# v0_9.net
KiCad netlist of a schematic drawn in EAGLE
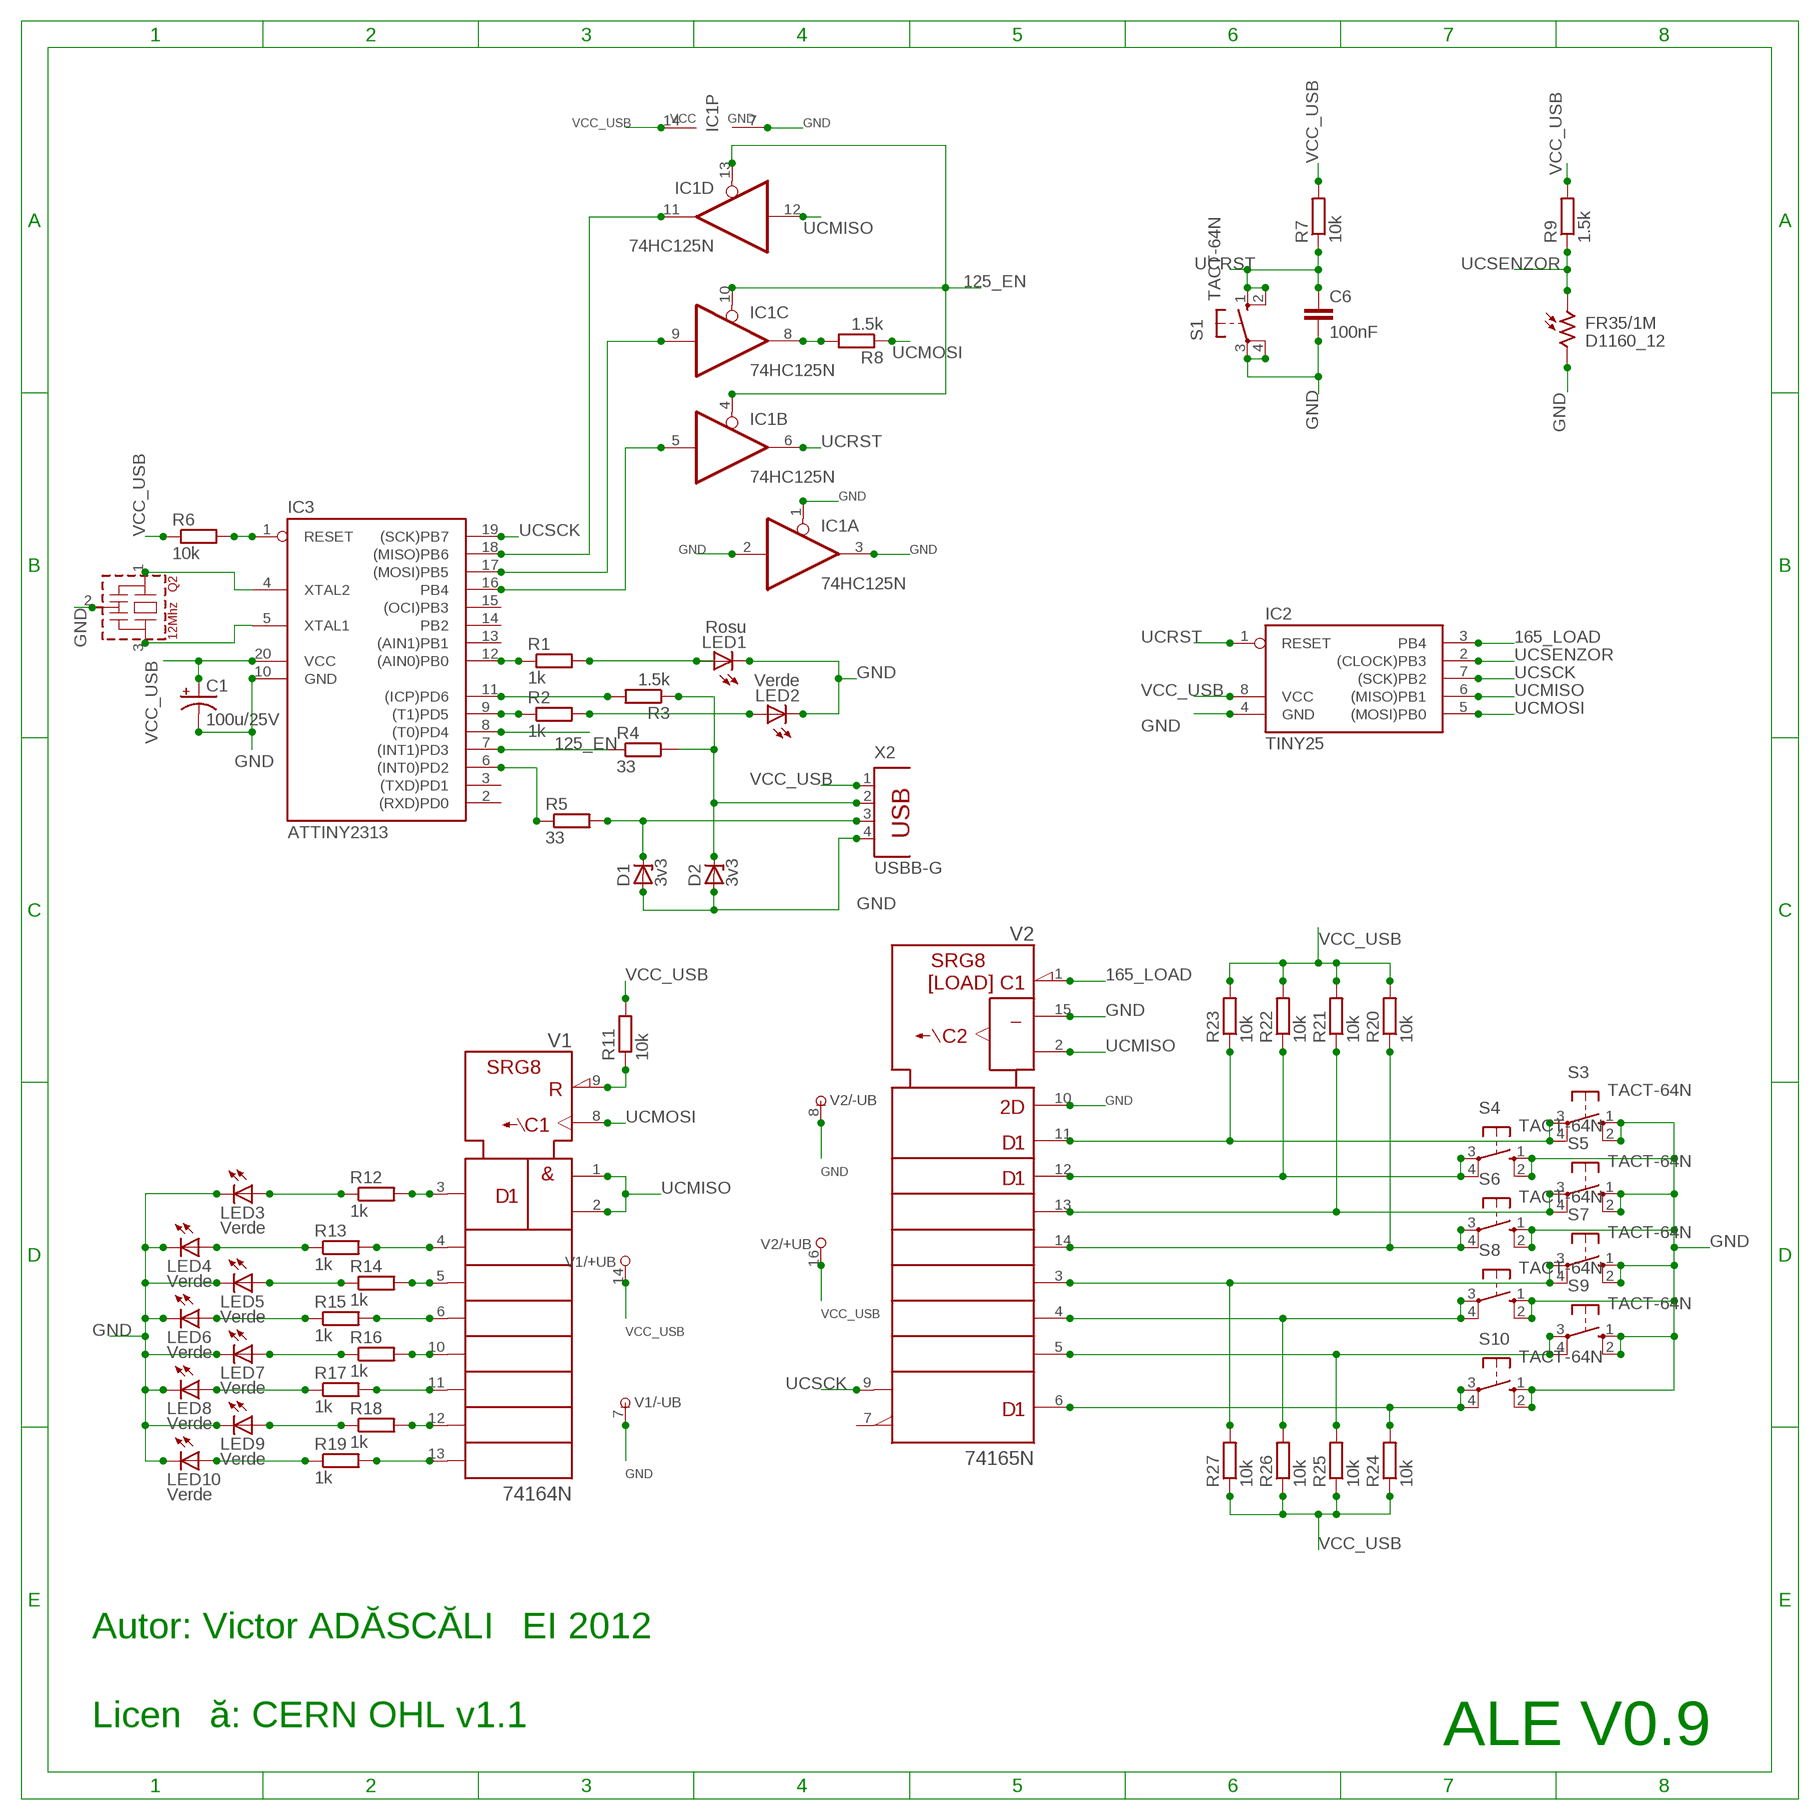
[diagram p0: schematic, sheet 1]

(export (version "E")
  (design (tool "Eeschema 10.0.6"))
  (components
    (comp (ref "C1")
      (value "100u/25V")
      (footprint "eagle-import:E2,5-6")
      (libsource (lib "eagle-import") (part "CPOL-USE2.5-6"))
    )
    (comp (ref "C6")
      (value "100nF")
      (footprint "eagle-import:C050-025X075")
      (libsource (lib "eagle-import") (part "C-EU050-025X075"))
    )
    (comp (ref "D1")
      (value "3v3")
      (footprint "eagle-import:ZDIO-7.5")
      (libsource (lib "eagle-import") (part "ZENER-DIODEZD-7.5"))
    )
    (comp (ref "D2")
      (value "3v3")
      (footprint "eagle-import:ZDIO-7.5")
      (libsource (lib "eagle-import") (part "ZENER-DIODEZD-7.5"))
    )
    (comp (ref "FR35/1M")
      (value "D1160_12")
      (footprint "eagle-import:D11XX")
      (libsource (lib "eagle-import") (part "D1160_12"))
    )
    (comp (ref "IC1")
      (value "74HC125N")
      (footprint "eagle-import:DIL14")
      (libsource (lib "eagle-import") (part "74125NAC"))
    )
    (comp (ref "IC2")
      (value "TINY25")
      (footprint "eagle-import:DIL08")
      (libsource (lib "eagle-import") (part "TINY22P"))
    )
    (comp (ref "IC3")
      (value "ATTINY2313")
      (footprint "eagle-import:DIL20")
      (libsource (lib "eagle-import") (part "AT90S2313P"))
    )
    (comp (ref "LED1")
      (value "Rosu")
      (footprint "eagle-import:LED3MM")
      (libsource (lib "eagle-import") (part "LED3MM"))
    )
    (comp (ref "LED2")
      (value "Verde")
      (footprint "eagle-import:LED3MM")
      (libsource (lib "eagle-import") (part "LED3MM"))
    )
    (comp (ref "LED3")
      (value "Verde")
      (footprint "eagle-import:LED3MM")
      (libsource (lib "eagle-import") (part "LED3MM"))
    )
    (comp (ref "LED4")
      (value "Verde")
      (footprint "eagle-import:LED3MM")
      (libsource (lib "eagle-import") (part "LED3MM"))
    )
    (comp (ref "LED5")
      (value "Verde")
      (footprint "eagle-import:LED3MM")
      (libsource (lib "eagle-import") (part "LED3MM"))
    )
    (comp (ref "LED6")
      (value "Verde")
      (footprint "eagle-import:LED3MM")
      (libsource (lib "eagle-import") (part "LED3MM"))
    )
    (comp (ref "LED7")
      (value "Verde")
      (footprint "eagle-import:LED3MM")
      (libsource (lib "eagle-import") (part "LED3MM"))
    )
    (comp (ref "LED8")
      (value "Verde")
      (footprint "eagle-import:LED3MM")
      (libsource (lib "eagle-import") (part "LED3MM"))
    )
    (comp (ref "LED9")
      (value "Verde")
      (footprint "eagle-import:LED3MM")
      (libsource (lib "eagle-import") (part "LED3MM"))
    )
    (comp (ref "LED10")
      (value "Verde")
      (footprint "eagle-import:LED3MM")
      (libsource (lib "eagle-import") (part "LED3MM"))
    )
    (comp (ref "Q2")
      (value "12Mhz")
      (footprint "eagle-import:CSTLS_X")
      (libsource (lib "eagle-import") (part "CSTLS_X"))
    )
    (comp (ref "R1")
      (value "1k")
      (footprint "eagle-import:0207_10")
      (libsource (lib "eagle-import") (part "R-EU_0207/10"))
    )
    (comp (ref "R2")
      (value "1k")
      (footprint "eagle-import:0204_5")
      (libsource (lib "eagle-import") (part "R-EU_0204/5"))
    )
    (comp (ref "R3")
      (value "1.5k")
      (footprint "eagle-import:0207_10")
      (libsource (lib "eagle-import") (part "R-EU_0207/10"))
    )
    (comp (ref "R4")
      (value "33")
      (footprint "eagle-import:0207_12")
      (libsource (lib "eagle-import") (part "R-EU_0207/12"))
    )
    (comp (ref "R5")
      (value "33")
      (footprint "eagle-import:0207_10")
      (libsource (lib "eagle-import") (part "R-EU_0207/10"))
    )
    (comp (ref "R6")
      (value "10k")
      (footprint "eagle-import:0207_10")
      (libsource (lib "eagle-import") (part "R-EU_0207/10"))
    )
    (comp (ref "R7")
      (value "10k")
      (footprint "eagle-import:0207_10")
      (libsource (lib "eagle-import") (part "R-EU_0207/10"))
    )
    (comp (ref "R8")
      (value "1.5k")
      (footprint "eagle-import:0207_10")
      (libsource (lib "eagle-import") (part "R-EU_0207/10"))
    )
    (comp (ref "R9")
      (value "1.5k")
      (footprint "eagle-import:0207_12")
      (libsource (lib "eagle-import") (part "R-EU_0207/12"))
    )
    (comp (ref "R11")
      (value "10k")
      (footprint "eagle-import:0207_15")
      (libsource (lib "eagle-import") (part "R-EU_0207/15"))
    )
    (comp (ref "R12")
      (value "1k")
      (footprint "eagle-import:0207_10")
      (libsource (lib "eagle-import") (part "R-EU_0207/10"))
    )
    (comp (ref "R13")
      (value "1k")
      (footprint "eagle-import:0207_10")
      (libsource (lib "eagle-import") (part "R-EU_0207/10"))
    )
    (comp (ref "R14")
      (value "1k")
      (footprint "eagle-import:0207_10")
      (libsource (lib "eagle-import") (part "R-EU_0207/10"))
    )
    (comp (ref "R15")
      (value "1k")
      (footprint "eagle-import:0207_10")
      (libsource (lib "eagle-import") (part "R-EU_0207/10"))
    )
    (comp (ref "R16")
      (value "1k")
      (footprint "eagle-import:0207_10")
      (libsource (lib "eagle-import") (part "R-EU_0207/10"))
    )
    (comp (ref "R17")
      (value "1k")
      (footprint "eagle-import:0207_10")
      (libsource (lib "eagle-import") (part "R-EU_0207/10"))
    )
    (comp (ref "R18")
      (value "1k")
      (footprint "eagle-import:0207_10")
      (libsource (lib "eagle-import") (part "R-EU_0207/10"))
    )
    (comp (ref "R19")
      (value "1k")
      (footprint "eagle-import:0207_10")
      (libsource (lib "eagle-import") (part "R-EU_0207/10"))
    )
    (comp (ref "R20")
      (value "10k")
      (footprint "eagle-import:0207_10")
      (libsource (lib "eagle-import") (part "R-EU_0207/10"))
    )
    (comp (ref "R21")
      (value "10k")
      (footprint "eagle-import:0207_10")
      (libsource (lib "eagle-import") (part "R-EU_0207/10"))
    )
    (comp (ref "R22")
      (value "10k")
      (footprint "eagle-import:0207_10")
      (libsource (lib "eagle-import") (part "R-EU_0207/10"))
    )
    (comp (ref "R23")
      (value "10k")
      (footprint "eagle-import:0207_10")
      (libsource (lib "eagle-import") (part "R-EU_0207/10"))
    )
    (comp (ref "R24")
      (value "10k")
      (footprint "eagle-import:0207_10")
      (libsource (lib "eagle-import") (part "R-EU_0207/10"))
    )
    (comp (ref "R25")
      (value "10k")
      (footprint "eagle-import:0207_10")
      (libsource (lib "eagle-import") (part "R-EU_0207/10"))
    )
    (comp (ref "R26")
      (value "10k")
      (footprint "eagle-import:0207_10")
      (libsource (lib "eagle-import") (part "R-EU_0207/10"))
    )
    (comp (ref "R27")
      (value "10k")
      (footprint "eagle-import:0207_10")
      (libsource (lib "eagle-import") (part "R-EU_0207/10"))
    )
    (comp (ref "S1")
      (value "TACT-64N")
      (footprint "eagle-import:B3F-10XX")
      (libsource (lib "eagle-import") (part "10-XX"))
    )
    (comp (ref "S3")
      (value "TACT-64N")
      (footprint "eagle-import:B3F-10XX")
      (libsource (lib "eagle-import") (part "10-XX"))
    )
    (comp (ref "S4")
      (value "TACT-64N")
      (footprint "eagle-import:B3F-10XX")
      (libsource (lib "eagle-import") (part "10-XX"))
    )
    (comp (ref "S5")
      (value "TACT-64N")
      (footprint "eagle-import:B3F-10XX")
      (libsource (lib "eagle-import") (part "10-XX"))
    )
    (comp (ref "S6")
      (value "TACT-64N")
      (footprint "eagle-import:B3F-10XX")
      (libsource (lib "eagle-import") (part "10-XX"))
    )
    (comp (ref "S7")
      (value "TACT-64N")
      (footprint "eagle-import:B3F-10XX")
      (libsource (lib "eagle-import") (part "10-XX"))
    )
    (comp (ref "S8")
      (value "TACT-64N")
      (footprint "eagle-import:B3F-10XX")
      (libsource (lib "eagle-import") (part "10-XX"))
    )
    (comp (ref "S9")
      (value "TACT-64N")
      (footprint "eagle-import:B3F-10XX")
      (libsource (lib "eagle-import") (part "10-XX"))
    )
    (comp (ref "S10")
      (value "TACT-64N")
      (footprint "eagle-import:B3F-10XX")
      (libsource (lib "eagle-import") (part "10-XX"))
    )
    (comp (ref "V1")
      (value "74164N")
      (footprint "eagle-import:DIL14")
      (libsource (lib "eagle-import") (part "74164N"))
    )
    (comp (ref "V2")
      (value "74165N")
      (footprint "eagle-import:DIL16")
      (libsource (lib "eagle-import") (part "74165N"))
    )
    (comp (ref "X2")
      (value "USBB-G")
      (footprint "eagle-import:PN61729")
      (libsource (lib "eagle-import") (part "PN61729"))
    )
  )
  (nets
    (net (code "1") (name "/125_EN") (class "Default")
      (node (ref "IC1") (pin "10") (pinfunction "OE_10") (pintype "input"))
      (node (ref "IC1") (pin "13") (pinfunction "OE_13") (pintype "input"))
      (node (ref "IC1") (pin "4") (pinfunction "OE_4") (pintype "input"))
      (node (ref "IC3") (pin "8") (pinfunction "(T0)PD4_8") (pintype "bidirectional"))
    )
    (net (code "2") (name "/165_LOAD") (class "Default")
      (node (ref "IC2") (pin "3") (pinfunction "PB4_3") (pintype "bidirectional"))
      (node (ref "V2") (pin "1") (pinfunction "SH/~{LD}_1") (pintype "input"))
    )
    (net (code "3") (name "/GND") (class "Default")
      (node (ref "C1") (pin "-") (pinfunction "-_-") (pintype "passive"))
      (node (ref "C6") (pin "2") (pinfunction "2_2") (pintype "passive"))
      (node (ref "D1") (pin "A") (pinfunction "A_A") (pintype "passive"))
      (node (ref "D2") (pin "A") (pinfunction "A_A") (pintype "passive"))
      (node (ref "FR35/1M") (pin "2") (pinfunction "2_2") (pintype "passive"))
      (node (ref "IC1") (pin "1") (pinfunction "OE_1") (pintype "input"))
      (node (ref "IC1") (pin "2") (pinfunction "I_2") (pintype "input"))
      (node (ref "IC1") (pin "3") (pinfunction "O_3") (pintype "tri_state"))
      (node (ref "IC1") (pin "7") (pinfunction "GND_7") (pintype "power_in"))
      (node (ref "IC2") (pin "4") (pinfunction "GND_4") (pintype "power_in"))
      (node (ref "IC3") (pin "10") (pinfunction "GND_10") (pintype "power_in"))
      (node (ref "LED1") (pin "K") (pinfunction "C_K") (pintype "passive"))
      (node (ref "LED10") (pin "K") (pinfunction "C_K") (pintype "passive"))
      (node (ref "LED2") (pin "K") (pinfunction "C_K") (pintype "passive"))
      (node (ref "LED3") (pin "K") (pinfunction "C_K") (pintype "passive"))
      (node (ref "LED4") (pin "K") (pinfunction "C_K") (pintype "passive"))
      (node (ref "LED5") (pin "K") (pinfunction "C_K") (pintype "passive"))
      (node (ref "LED6") (pin "K") (pinfunction "C_K") (pintype "passive"))
      (node (ref "LED7") (pin "K") (pinfunction "C_K") (pintype "passive"))
      (node (ref "LED8") (pin "K") (pinfunction "C_K") (pintype "passive"))
      (node (ref "LED9") (pin "K") (pinfunction "C_K") (pintype "passive"))
      (node (ref "Q2") (pin "2") (pinfunction "VSS_2") (pintype "power_in"))
      (node (ref "S1") (pin "3") (pinfunction "P_3") (pintype "passive"))
      (node (ref "S1") (pin "4") (pinfunction "P1_4") (pintype "passive"))
      (node (ref "S10") (pin "1") (pinfunction "S_1") (pintype "passive"))
      (node (ref "S10") (pin "2") (pinfunction "S1_2") (pintype "passive"))
      (node (ref "S3") (pin "1") (pinfunction "S_1") (pintype "passive"))
      (node (ref "S3") (pin "2") (pinfunction "S1_2") (pintype "passive"))
      (node (ref "S4") (pin "1") (pinfunction "S_1") (pintype "passive"))
      (node (ref "S4") (pin "2") (pinfunction "S1_2") (pintype "passive"))
      (node (ref "S5") (pin "1") (pinfunction "S_1") (pintype "passive"))
      (node (ref "S5") (pin "2") (pinfunction "S1_2") (pintype "passive"))
      (node (ref "S6") (pin "1") (pinfunction "S_1") (pintype "passive"))
      (node (ref "S6") (pin "2") (pinfunction "S1_2") (pintype "passive"))
      (node (ref "S7") (pin "1") (pinfunction "S_1") (pintype "passive"))
      (node (ref "S7") (pin "2") (pinfunction "S1_2") (pintype "passive"))
      (node (ref "S8") (pin "1") (pinfunction "S_1") (pintype "passive"))
      (node (ref "S8") (pin "2") (pinfunction "S1_2") (pintype "passive"))
      (node (ref "S9") (pin "1") (pinfunction "S_1") (pintype "passive"))
      (node (ref "S9") (pin "2") (pinfunction "S1_2") (pintype "passive"))
      (node (ref "V1") (pin "7") (pinfunction "-UB_7") (pintype "power_in"))
      (node (ref "V2") (pin "10") (pinfunction "SER_10") (pintype "input"))
      (node (ref "V2") (pin "15") (pinfunction "CLK_INH_15") (pintype "input"))
      (node (ref "V2") (pin "8") (pinfunction "-UB_8") (pintype "power_in"))
      (node (ref "X2") (pin "4") (pinfunction "4_4") (pintype "passive"))
    )
    (net (code "4") (name "/UCMISO") (class "Default")
      (node (ref "IC1") (pin "12") (pinfunction "I_12") (pintype "input"))
      (node (ref "IC2") (pin "6") (pinfunction "(MISO)PB1_6") (pintype "bidirectional"))
      (node (ref "V1") (pin "1") (pinfunction "A_1") (pintype "input"))
      (node (ref "V1") (pin "2") (pinfunction "B_2") (pintype "input"))
      (node (ref "V2") (pin "2") (pinfunction "CLK_2") (pintype "input"))
    )
    (net (code "5") (name "/UCMOSI") (class "Default")
      (node (ref "IC2") (pin "5") (pinfunction "(MOSI)PB0_5") (pintype "bidirectional"))
      (node (ref "R8") (pin "1") (pinfunction "1_1") (pintype "passive"))
      (node (ref "V1") (pin "8") (pinfunction "CLK_8") (pintype "input"))
    )
    (net (code "6") (name "/UCRST") (class "Default")
      (node (ref "C6") (pin "1") (pinfunction "1_1") (pintype "passive"))
      (node (ref "IC1") (pin "6") (pinfunction "O_6") (pintype "tri_state"))
      (node (ref "IC2") (pin "1") (pinfunction "RESET_1") (pintype "input"))
      (node (ref "R7") (pin "1") (pinfunction "1_1") (pintype "passive"))
      (node (ref "S1") (pin "1") (pinfunction "S_1") (pintype "passive"))
      (node (ref "S1") (pin "2") (pinfunction "S1_2") (pintype "passive"))
    )
    (net (code "7") (name "/UCSCK") (class "Default")
      (node (ref "IC2") (pin "7") (pinfunction "(SCK)PB2_7") (pintype "bidirectional"))
      (node (ref "IC3") (pin "19") (pinfunction "(SCK)PB7_19") (pintype "bidirectional"))
      (node (ref "V2") (pin "9") (pinfunction "QH_9") (pintype "output"))
    )
    (net (code "8") (name "/UCSENZOR") (class "Default")
      (node (ref "FR35/1M") (pin "1") (pinfunction "1_1") (pintype "passive"))
      (node (ref "IC2") (pin "2") (pinfunction "(CLOCK)PB3_2") (pintype "bidirectional"))
      (node (ref "R9") (pin "1") (pinfunction "1_1") (pintype "passive"))
    )
    (net (code "9") (name "/VCC_USB") (class "Default")
      (node (ref "C1") (pin "+") (pinfunction "+_+") (pintype "passive"))
      (node (ref "IC1") (pin "14") (pinfunction "VCC_14") (pintype "power_in"))
      (node (ref "IC2") (pin "8") (pinfunction "VCC_8") (pintype "power_in"))
      (node (ref "IC3") (pin "20") (pinfunction "VCC_20") (pintype "power_in"))
      (node (ref "R11") (pin "2") (pinfunction "2_2") (pintype "passive"))
      (node (ref "R20") (pin "2") (pinfunction "2_2") (pintype "passive"))
      (node (ref "R21") (pin "2") (pinfunction "2_2") (pintype "passive"))
      (node (ref "R22") (pin "2") (pinfunction "2_2") (pintype "passive"))
      (node (ref "R23") (pin "2") (pinfunction "2_2") (pintype "passive"))
      (node (ref "R24") (pin "1") (pinfunction "1_1") (pintype "passive"))
      (node (ref "R25") (pin "1") (pinfunction "1_1") (pintype "passive"))
      (node (ref "R26") (pin "1") (pinfunction "1_1") (pintype "passive"))
      (node (ref "R27") (pin "1") (pinfunction "1_1") (pintype "passive"))
      (node (ref "R6") (pin "1") (pinfunction "1_1") (pintype "passive"))
      (node (ref "R7") (pin "2") (pinfunction "2_2") (pintype "passive"))
      (node (ref "R9") (pin "2") (pinfunction "2_2") (pintype "passive"))
      (node (ref "V1") (pin "14") (pinfunction "+UB_14") (pintype "power_in"))
      (node (ref "V2") (pin "16") (pinfunction "+UB_16") (pintype "power_in"))
      (node (ref "X2") (pin "1") (pinfunction "1_1") (pintype "passive"))
    )
    (net (code "10") (name "Net-(D1-PadC)") (class "Default")
      (node (ref "D1") (pin "C") (pinfunction "C_C") (pintype "passive"))
      (node (ref "R5") (pin "2") (pinfunction "2_2") (pintype "passive"))
      (node (ref "X2") (pin "3") (pinfunction "3_3") (pintype "passive"))
    )
    (net (code "11") (name "Net-(D2-PadC)") (class "Default")
      (node (ref "D2") (pin "C") (pinfunction "C_C") (pintype "passive"))
      (node (ref "R3") (pin "1") (pinfunction "1_1") (pintype "passive"))
      (node (ref "R4") (pin "2") (pinfunction "2_2") (pintype "passive"))
      (node (ref "X2") (pin "2") (pinfunction "2_2") (pintype "passive"))
    )
    (net (code "12") (name "Net-(IC1B-I)") (class "Default")
      (node (ref "IC1") (pin "5") (pinfunction "I_5") (pintype "input"))
      (node (ref "IC3") (pin "16") (pinfunction "PB4_16") (pintype "bidirectional"))
    )
    (net (code "13") (name "Net-(IC1C-I)") (class "Default")
      (node (ref "IC1") (pin "9") (pinfunction "I_9") (pintype "input"))
      (node (ref "IC3") (pin "17") (pinfunction "(MOSI)PB5_17") (pintype "bidirectional"))
    )
    (net (code "14") (name "Net-(IC1C-O)") (class "Default")
      (node (ref "IC1") (pin "8") (pinfunction "O_8") (pintype "tri_state"))
      (node (ref "R8") (pin "2") (pinfunction "2_2") (pintype "passive"))
    )
    (net (code "15") (name "Net-(IC1D-O)") (class "Default")
      (node (ref "IC1") (pin "11") (pinfunction "O_11") (pintype "tri_state"))
      (node (ref "IC3") (pin "18") (pinfunction "(MISO)PB6_18") (pintype "bidirectional"))
    )
    (net (code "16") (name "Net-(IC3-(AIN0)PB0)") (class "Default")
      (node (ref "IC3") (pin "12") (pinfunction "(AIN0)PB0_12") (pintype "bidirectional"))
      (node (ref "R1") (pin "1") (pinfunction "1_1") (pintype "passive"))
    )
    (net (code "17") (name "Net-(IC3-(ICP)PD6)") (class "Default")
      (node (ref "IC3") (pin "11") (pinfunction "(ICP)PD6_11") (pintype "bidirectional"))
      (node (ref "R3") (pin "2") (pinfunction "2_2") (pintype "passive"))
    )
    (net (code "18") (name "Net-(IC3-(INT0)PD2)") (class "Default")
      (node (ref "IC3") (pin "6") (pinfunction "(INT0)PD2_6") (pintype "bidirectional"))
      (node (ref "R5") (pin "1") (pinfunction "1_1") (pintype "passive"))
    )
    (net (code "19") (name "Net-(IC3-(INT1)PD3)") (class "Default")
      (node (ref "IC3") (pin "7") (pinfunction "(INT1)PD3_7") (pintype "bidirectional"))
      (node (ref "R4") (pin "1") (pinfunction "1_1") (pintype "passive"))
    )
    (net (code "20") (name "Net-(IC3-(T1)PD5)") (class "Default")
      (node (ref "IC3") (pin "9") (pinfunction "(T1)PD5_9") (pintype "bidirectional"))
      (node (ref "R2") (pin "1") (pinfunction "1_1") (pintype "passive"))
    )
    (net (code "21") (name "Net-(IC3-RESET)") (class "Default")
      (node (ref "IC3") (pin "1") (pinfunction "RESET_1") (pintype "bidirectional"))
      (node (ref "R6") (pin "2") (pinfunction "2_2") (pintype "passive"))
    )
    (net (code "22") (name "Net-(IC3-XTAL1)") (class "Default")
      (node (ref "IC3") (pin "5") (pinfunction "XTAL1_5") (pintype "bidirectional"))
      (node (ref "Q2") (pin "3") (pinfunction "3_3") (pintype "input"))
    )
    (net (code "23") (name "Net-(IC3-XTAL2)") (class "Default")
      (node (ref "IC3") (pin "4") (pinfunction "XTAL2_4") (pintype "bidirectional"))
      (node (ref "Q2") (pin "1") (pinfunction "1_1") (pintype "output"))
    )
    (net (code "24") (name "Net-(LED1-PadA)") (class "Default")
      (node (ref "LED1") (pin "A") (pinfunction "A_A") (pintype "passive"))
      (node (ref "R1") (pin "2") (pinfunction "2_2") (pintype "passive"))
    )
    (net (code "25") (name "Net-(LED2-PadA)") (class "Default")
      (node (ref "LED2") (pin "A") (pinfunction "A_A") (pintype "passive"))
      (node (ref "R2") (pin "2") (pinfunction "2_2") (pintype "passive"))
    )
    (net (code "26") (name "Net-(LED3-PadA)") (class "Default")
      (node (ref "LED3") (pin "A") (pinfunction "A_A") (pintype "passive"))
      (node (ref "R12") (pin "1") (pinfunction "1_1") (pintype "passive"))
    )
    (net (code "27") (name "Net-(LED4-PadA)") (class "Default")
      (node (ref "LED4") (pin "A") (pinfunction "A_A") (pintype "passive"))
      (node (ref "R13") (pin "1") (pinfunction "1_1") (pintype "passive"))
    )
    (net (code "28") (name "Net-(LED5-PadA)") (class "Default")
      (node (ref "LED5") (pin "A") (pinfunction "A_A") (pintype "passive"))
      (node (ref "R14") (pin "1") (pinfunction "1_1") (pintype "passive"))
    )
    (net (code "29") (name "Net-(LED6-PadA)") (class "Default")
      (node (ref "LED6") (pin "A") (pinfunction "A_A") (pintype "passive"))
      (node (ref "R15") (pin "1") (pinfunction "1_1") (pintype "passive"))
    )
    (net (code "30") (name "Net-(LED7-PadA)") (class "Default")
      (node (ref "LED7") (pin "A") (pinfunction "A_A") (pintype "passive"))
      (node (ref "R16") (pin "1") (pinfunction "1_1") (pintype "passive"))
    )
    (net (code "31") (name "Net-(LED8-PadA)") (class "Default")
      (node (ref "LED8") (pin "A") (pinfunction "A_A") (pintype "passive"))
      (node (ref "R17") (pin "1") (pinfunction "1_1") (pintype "passive"))
    )
    (net (code "32") (name "Net-(LED9-PadA)") (class "Default")
      (node (ref "LED9") (pin "A") (pinfunction "A_A") (pintype "passive"))
      (node (ref "R18") (pin "1") (pinfunction "1_1") (pintype "passive"))
    )
    (net (code "33") (name "Net-(LED10-PadA)") (class "Default")
      (node (ref "LED10") (pin "A") (pinfunction "A_A") (pintype "passive"))
      (node (ref "R19") (pin "1") (pinfunction "1_1") (pintype "passive"))
    )
    (net (code "34") (name "Net-(S3-P)") (class "Default")
      (node (ref "R23") (pin "1") (pinfunction "1_1") (pintype "passive"))
      (node (ref "S3") (pin "3") (pinfunction "P_3") (pintype "passive"))
      (node (ref "S3") (pin "4") (pinfunction "P1_4") (pintype "passive"))
      (node (ref "V2") (pin "11") (pinfunction "A_11") (pintype "input"))
    )
    (net (code "35") (name "Net-(S4-P)") (class "Default")
      (node (ref "R22") (pin "1") (pinfunction "1_1") (pintype "passive"))
      (node (ref "S4") (pin "3") (pinfunction "P_3") (pintype "passive"))
      (node (ref "S4") (pin "4") (pinfunction "P1_4") (pintype "passive"))
      (node (ref "V2") (pin "12") (pinfunction "B_12") (pintype "input"))
    )
    (net (code "36") (name "Net-(S5-P)") (class "Default")
      (node (ref "R21") (pin "1") (pinfunction "1_1") (pintype "passive"))
      (node (ref "S5") (pin "3") (pinfunction "P_3") (pintype "passive"))
      (node (ref "S5") (pin "4") (pinfunction "P1_4") (pintype "passive"))
      (node (ref "V2") (pin "13") (pinfunction "C_13") (pintype "input"))
    )
    (net (code "37") (name "Net-(S6-P)") (class "Default")
      (node (ref "R20") (pin "1") (pinfunction "1_1") (pintype "passive"))
      (node (ref "S6") (pin "3") (pinfunction "P_3") (pintype "passive"))
      (node (ref "S6") (pin "4") (pinfunction "P1_4") (pintype "passive"))
      (node (ref "V2") (pin "14") (pinfunction "D_14") (pintype "input"))
    )
    (net (code "38") (name "Net-(S7-P)") (class "Default")
      (node (ref "R27") (pin "2") (pinfunction "2_2") (pintype "passive"))
      (node (ref "S7") (pin "3") (pinfunction "P_3") (pintype "passive"))
      (node (ref "S7") (pin "4") (pinfunction "P1_4") (pintype "passive"))
      (node (ref "V2") (pin "3") (pinfunction "E_3") (pintype "input"))
    )
    (net (code "39") (name "Net-(S8-P)") (class "Default")
      (node (ref "R26") (pin "2") (pinfunction "2_2") (pintype "passive"))
      (node (ref "S8") (pin "3") (pinfunction "P_3") (pintype "passive"))
      (node (ref "S8") (pin "4") (pinfunction "P1_4") (pintype "passive"))
      (node (ref "V2") (pin "4") (pinfunction "F_4") (pintype "input"))
    )
    (net (code "40") (name "Net-(S9-P)") (class "Default")
      (node (ref "R25") (pin "2") (pinfunction "2_2") (pintype "passive"))
      (node (ref "S9") (pin "3") (pinfunction "P_3") (pintype "passive"))
      (node (ref "S9") (pin "4") (pinfunction "P1_4") (pintype "passive"))
      (node (ref "V2") (pin "5") (pinfunction "G_5") (pintype "input"))
    )
    (net (code "41") (name "Net-(S10-P)") (class "Default")
      (node (ref "R24") (pin "2") (pinfunction "2_2") (pintype "passive"))
      (node (ref "S10") (pin "3") (pinfunction "P_3") (pintype "passive"))
      (node (ref "S10") (pin "4") (pinfunction "P1_4") (pintype "passive"))
      (node (ref "V2") (pin "6") (pinfunction "H_6") (pintype "input"))
    )
    (net (code "42") (name "Net-(V1C-QA)") (class "Default")
      (node (ref "R12") (pin "2") (pinfunction "2_2") (pintype "passive"))
      (node (ref "V1") (pin "3") (pinfunction "QA_3") (pintype "output"))
    )
    (net (code "43") (name "Net-(V1C-QB)") (class "Default")
      (node (ref "R13") (pin "2") (pinfunction "2_2") (pintype "passive"))
      (node (ref "V1") (pin "4") (pinfunction "QB_4") (pintype "output"))
    )
    (net (code "44") (name "Net-(V1C-QC)") (class "Default")
      (node (ref "R14") (pin "2") (pinfunction "2_2") (pintype "passive"))
      (node (ref "V1") (pin "5") (pinfunction "QC_5") (pintype "output"))
    )
    (net (code "45") (name "Net-(V1C-QD)") (class "Default")
      (node (ref "R15") (pin "2") (pinfunction "2_2") (pintype "passive"))
      (node (ref "V1") (pin "6") (pinfunction "QD_6") (pintype "output"))
    )
    (net (code "46") (name "Net-(V1C-QE)") (class "Default")
      (node (ref "R16") (pin "2") (pinfunction "2_2") (pintype "passive"))
      (node (ref "V1") (pin "10") (pinfunction "QE_10") (pintype "output"))
    )
    (net (code "47") (name "Net-(V1C-QF)") (class "Default")
      (node (ref "R17") (pin "2") (pinfunction "2_2") (pintype "passive"))
      (node (ref "V1") (pin "11") (pinfunction "QF_11") (pintype "output"))
    )
    (net (code "48") (name "Net-(V1C-QG)") (class "Default")
      (node (ref "R18") (pin "2") (pinfunction "2_2") (pintype "passive"))
      (node (ref "V1") (pin "12") (pinfunction "QG_12") (pintype "output"))
    )
    (net (code "49") (name "Net-(V1C-QH)") (class "Default")
      (node (ref "R19") (pin "2") (pinfunction "2_2") (pintype "passive"))
      (node (ref "V1") (pin "13") (pinfunction "QH_13") (pintype "output"))
    )
    (net (code "50") (name "Net-(V1C-~{CLR})") (class "Default")
      (node (ref "R11") (pin "1") (pinfunction "1_1") (pintype "passive"))
      (node (ref "V1") (pin "9") (pinfunction "~{CLR}_9") (pintype "input"))
    )
    (net (code "51") (name "unconnected-(IC3-(AIN1)PB1-Pad13)") (class "Default")
      (node (ref "IC3") (pin "13") (pinfunction "(AIN1)PB1_13") (pintype "bidirectional"))
    )
    (net (code "52") (name "unconnected-(IC3-(OCI)PB3-Pad15)") (class "Default")
      (node (ref "IC3") (pin "15") (pinfunction "(OCI)PB3_15") (pintype "bidirectional"))
    )
    (net (code "53") (name "unconnected-(IC3-(RXD)PD0-Pad2)") (class "Default")
      (node (ref "IC3") (pin "2") (pinfunction "(RXD)PD0_2") (pintype "bidirectional"))
    )
    (net (code "54") (name "unconnected-(IC3-(TXD)PD1-Pad3)") (class "Default")
      (node (ref "IC3") (pin "3") (pinfunction "(TXD)PD1_3") (pintype "bidirectional"))
    )
    (net (code "55") (name "unconnected-(IC3-PB2-Pad14)") (class "Default")
      (node (ref "IC3") (pin "14") (pinfunction "PB2_14") (pintype "bidirectional"))
    )
    (net (code "56") (name "unconnected-(V2C-~{QH}-Pad7)") (class "Default")
      (node (ref "V2") (pin "7") (pinfunction "~{QH}_7") (pintype "output"))
    )
  )
)
